# ArduinoISP_32U4_v3.net
KiCad netlist of a schematic drawn in EAGLE
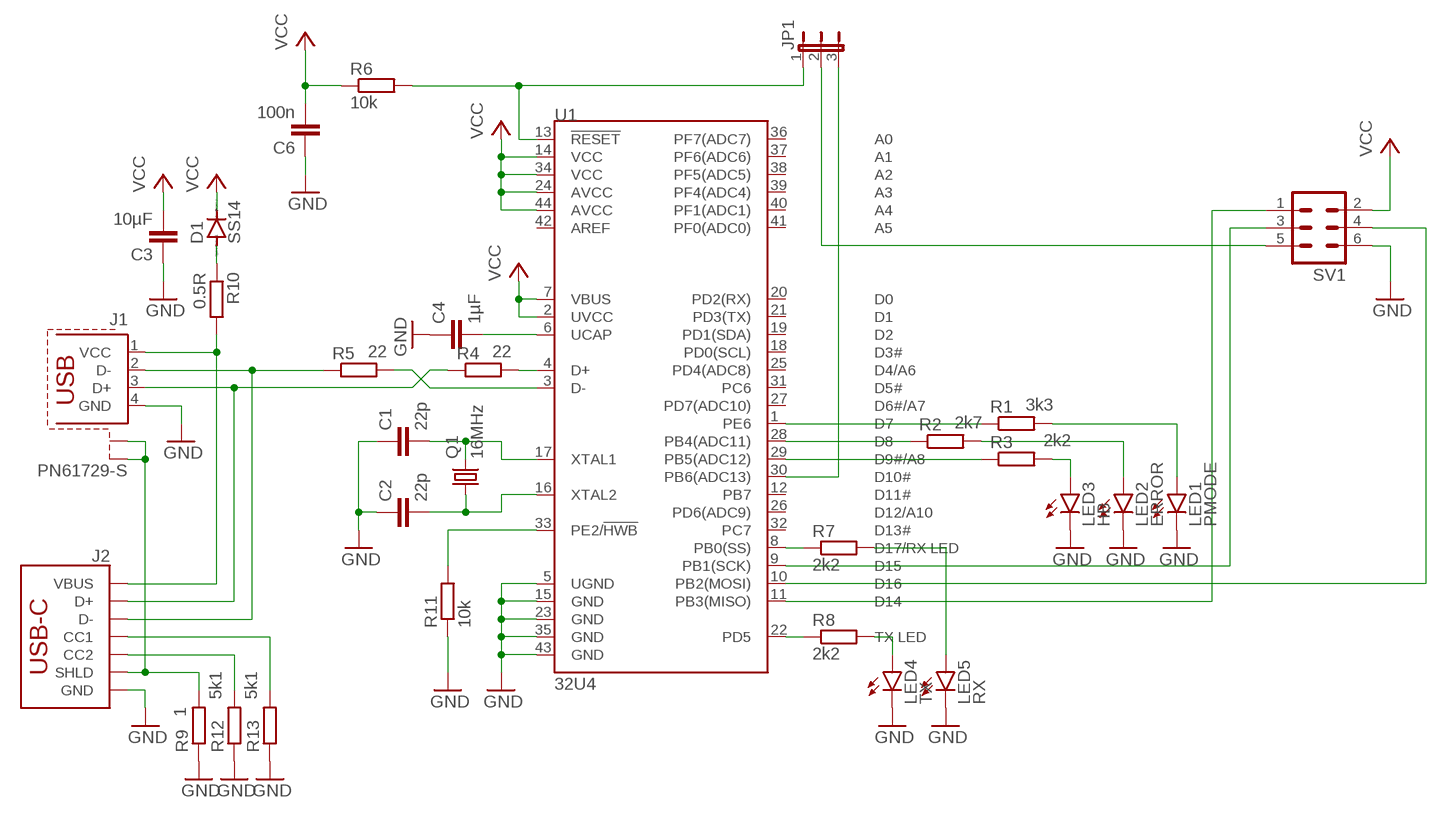
[diagram p0: schematic, sheet 1]

(export (version "E")
  (design (tool "Eeschema 10.0.6"))
  (components
    (comp (ref "C1")
      (value "22p")
      (footprint "eagle-import:C1206")
      (libsource (lib "eagle-import") (part "C-EUC1206"))
    )
    (comp (ref "C2")
      (value "22p")
      (footprint "eagle-import:C1206")
      (libsource (lib "eagle-import") (part "C-EUC1206"))
    )
    (comp (ref "C3")
      (value "10µF")
      (footprint "eagle-import:C1206")
      (libsource (lib "eagle-import") (part "C-EUC1206"))
    )
    (comp (ref "C4")
      (value "1µF")
      (footprint "eagle-import:C1206")
      (libsource (lib "eagle-import") (part "C-EUC1206"))
    )
    (comp (ref "C6")
      (value "100n")
      (footprint "eagle-import:C1206")
      (libsource (lib "eagle-import") (part "C-EUC1206"))
    )
    (comp (ref "D1")
      (value "SS14")
      (footprint "eagle-import:DO214AC")
      (libsource (lib "eagle-import") (part "DIODE-DO214AC"))
    )
    (comp (ref "J1")
      (value "PN61729-S")
      (footprint "eagle-import:PN61729-S")
      (libsource (lib "eagle-import") (part "PN61729-S"))
    )
    (comp (ref "J2")
      (value "USB_C_2-LAYER_PADS")
      (footprint "eagle-import:USB-C-16P-2LAYER-PADS")
      (libsource (lib "eagle-import") (part "USB_C_2-LAYER_PADS"))
    )
    (comp (ref "JP1")
      (value "JP2E")
      (footprint "eagle-import:JP2")
      (libsource (lib "eagle-import") (part "JP2E"))
    )
    (comp (ref "LED1")
      (value "PMODE")
      (footprint "eagle-import:CHIPLED_1206")
      (libsource (lib "eagle-import") (part "LEDCHIPLED_1206"))
    )
    (comp (ref "LED2")
      (value "ERROR")
      (footprint "eagle-import:CHIPLED_1206")
      (libsource (lib "eagle-import") (part "LEDCHIPLED_1206"))
    )
    (comp (ref "LED3")
      (value "HB")
      (footprint "eagle-import:CHIPLED_1206")
      (libsource (lib "eagle-import") (part "LEDCHIPLED_1206"))
    )
    (comp (ref "LED4")
      (value "TX")
      (footprint "eagle-import:CHIPLED_1206")
      (libsource (lib "eagle-import") (part "LEDCHIPLED_1206"))
    )
    (comp (ref "LED5")
      (value "RX")
      (footprint "eagle-import:CHIPLED_1206")
      (libsource (lib "eagle-import") (part "LEDCHIPLED_1206"))
    )
    (comp (ref "Q1")
      (value "16MHz")
      (footprint "eagle-import:HC49UP")
      (libsource (lib "eagle-import") (part "CRYSTALHC49UP"))
    )
    (comp (ref "R1")
      (value "3k3")
      (footprint "eagle-import:R1206")
      (libsource (lib "eagle-import") (part "R-EU_R1206"))
    )
    (comp (ref "R2")
      (value "2k7")
      (footprint "eagle-import:R1206")
      (libsource (lib "eagle-import") (part "R-EU_R1206"))
    )
    (comp (ref "R3")
      (value "2k2")
      (footprint "eagle-import:R1206")
      (libsource (lib "eagle-import") (part "R-EU_R1206"))
    )
    (comp (ref "R4")
      (value "22")
      (footprint "eagle-import:R1206")
      (libsource (lib "eagle-import") (part "R-EU_R1206"))
    )
    (comp (ref "R5")
      (value "22")
      (footprint "eagle-import:R1206")
      (libsource (lib "eagle-import") (part "R-EU_R1206"))
    )
    (comp (ref "R6")
      (value "10k")
      (footprint "eagle-import:R1206")
      (libsource (lib "eagle-import") (part "R-EU_R1206"))
    )
    (comp (ref "R7")
      (value "2k2")
      (footprint "eagle-import:R1206")
      (libsource (lib "eagle-import") (part "R-EU_R1206"))
    )
    (comp (ref "R8")
      (value "2k2")
      (footprint "eagle-import:R1206")
      (libsource (lib "eagle-import") (part "R-EU_R1206"))
    )
    (comp (ref "R9")
      (value "1")
      (footprint "eagle-import:R1206")
      (libsource (lib "eagle-import") (part "R-EU_R1206"))
    )
    (comp (ref "R10")
      (value "0.5R")
      (footprint "eagle-import:R1206")
      (libsource (lib "eagle-import") (part "R-EU_R1206"))
    )
    (comp (ref "R11")
      (value "10k")
      (footprint "eagle-import:R1206")
      (libsource (lib "eagle-import") (part "R-EU_R1206"))
    )
    (comp (ref "R12")
      (value "5k1")
      (footprint "eagle-import:R1206")
      (libsource (lib "eagle-import") (part "R-EU_R1206"))
    )
    (comp (ref "R13")
      (value "5k1")
      (footprint "eagle-import:R1206")
      (libsource (lib "eagle-import") (part "R-EU_R1206"))
    )
    (comp (ref "SV1")
      (value "ML6")
      (footprint "eagle-import:ML6")
      (libsource (lib "eagle-import") (part "ML6"))
    )
    (comp (ref "U1")
      (value "32U4")
      (footprint "eagle-import:TQFP44")
      (libsource (lib "eagle-import") (part "ATMEGA32U4TQFP-44"))
    )
  )
  (nets
    (net (code "1") (name "GND") (class "Default")
      (node (ref "C1") (pin "1") (pinfunction "1_1") (pintype "passive"))
      (node (ref "C2") (pin "1") (pinfunction "1_1") (pintype "passive"))
      (node (ref "C3") (pin "1") (pinfunction "1_1") (pintype "passive"))
      (node (ref "C4") (pin "1") (pinfunction "1_1") (pintype "passive"))
      (node (ref "C6") (pin "1") (pinfunction "1_1") (pintype "passive"))
      (node (ref "J1") (pin "4") (pinfunction "GND_4") (pintype "passive"))
      (node (ref "J2") (pin "GND") (pinfunction "GND_GND") (pintype "bidirectional"))
      (node (ref "J2") (pin "GND2") (pinfunction "GND_GND2") (pintype "bidirectional"))
      (node (ref "LED1") (pin "C") (pinfunction "C_C") (pintype "passive"))
      (node (ref "LED2") (pin "C") (pinfunction "C_C") (pintype "passive"))
      (node (ref "LED3") (pin "C") (pinfunction "C_C") (pintype "passive"))
      (node (ref "LED4") (pin "C") (pinfunction "C_C") (pintype "passive"))
      (node (ref "LED5") (pin "C") (pinfunction "C_C") (pintype "passive"))
      (node (ref "R11") (pin "1") (pinfunction "1_1") (pintype "passive"))
      (node (ref "R12") (pin "1") (pinfunction "1_1") (pintype "passive"))
      (node (ref "R13") (pin "1") (pinfunction "1_1") (pintype "passive"))
      (node (ref "R9") (pin "1") (pinfunction "1_1") (pintype "passive"))
      (node (ref "SV1") (pin "6") (pinfunction "6_6") (pintype "passive"))
      (node (ref "U1") (pin "15") (pinfunction "GND_15") (pintype "bidirectional"))
      (node (ref "U1") (pin "23") (pinfunction "GND_23") (pintype "bidirectional"))
      (node (ref "U1") (pin "35") (pinfunction "GND_35") (pintype "bidirectional"))
      (node (ref "U1") (pin "43") (pinfunction "GND_43") (pintype "bidirectional"))
      (node (ref "U1") (pin "5") (pinfunction "UGND_5") (pintype "bidirectional"))
    )
    (net (code "2") (name "Net-(D1-PadA)") (class "Default")
      (node (ref "D1") (pin "A") (pinfunction "A_A") (pintype "passive"))
      (node (ref "R10") (pin "1") (pinfunction "1_1") (pintype "passive"))
    )
    (net (code "3") (name "Net-(J1-D+)") (class "Default")
      (node (ref "J1") (pin "3") (pinfunction "D+_3") (pintype "passive"))
      (node (ref "J2") (pin "A6") (pinfunction "D+_A6") (pintype "bidirectional"))
      (node (ref "J2") (pin "B6") (pinfunction "D+_B6") (pintype "bidirectional"))
      (node (ref "R4") (pin "1") (pinfunction "1_1") (pintype "passive"))
    )
    (net (code "4") (name "Net-(J1-D-)") (class "Default")
      (node (ref "J1") (pin "2") (pinfunction "D-_2") (pintype "passive"))
      (node (ref "J2") (pin "A7") (pinfunction "D-_A7") (pintype "bidirectional"))
      (node (ref "J2") (pin "B7") (pinfunction "D-_B7") (pintype "bidirectional"))
      (node (ref "R5") (pin "1") (pinfunction "1_1") (pintype "passive"))
    )
    (net (code "5") (name "Net-(J1-PadS1)") (class "Default")
      (node (ref "J1") (pin "S1") (pinfunction "S1_S1") (pintype "passive"))
      (node (ref "J1") (pin "S2") (pinfunction "S2_S2") (pintype "passive"))
      (node (ref "J2") (pin "SHLD1") (pinfunction "SHLD_SHLD1") (pintype "bidirectional"))
      (node (ref "J2") (pin "SHLD2") (pinfunction "SHLD_SHLD2") (pintype "bidirectional"))
      (node (ref "J2") (pin "SHLD3") (pinfunction "SHLD_SHLD3") (pintype "bidirectional"))
      (node (ref "J2") (pin "SHLD4") (pinfunction "SHLD_SHLD4") (pintype "bidirectional"))
      (node (ref "R9") (pin "2") (pinfunction "2_2") (pintype "passive"))
    )
    (net (code "6") (name "Net-(J1-VCC)") (class "Default")
      (node (ref "J1") (pin "1") (pinfunction "VCC_1") (pintype "passive"))
      (node (ref "J2") (pin "VBUS1") (pinfunction "VBUS_VBUS1") (pintype "bidirectional"))
      (node (ref "J2") (pin "VBUS2") (pinfunction "VBUS_VBUS2") (pintype "bidirectional"))
      (node (ref "R10") (pin "2") (pinfunction "2_2") (pintype "passive"))
    )
    (net (code "7") (name "Net-(J2-CC1)") (class "Default")
      (node (ref "J2") (pin "A5") (pinfunction "CC1_A5") (pintype "bidirectional"))
      (node (ref "R13") (pin "2") (pinfunction "2_2") (pintype "passive"))
    )
    (net (code "8") (name "Net-(J2-CC2)") (class "Default")
      (node (ref "J2") (pin "B5") (pinfunction "CC2_B5") (pintype "bidirectional"))
      (node (ref "R12") (pin "2") (pinfunction "2_2") (pintype "passive"))
    )
    (net (code "9") (name "Net-(JP1-Pad2)") (class "Default")
      (node (ref "JP1") (pin "2") (pinfunction "2_2") (pintype "passive"))
      (node (ref "SV1") (pin "5") (pinfunction "5_5") (pintype "passive"))
    )
    (net (code "10") (name "Net-(LED1-PadA)") (class "Default")
      (node (ref "LED1") (pin "A") (pinfunction "A_A") (pintype "passive"))
      (node (ref "R1") (pin "2") (pinfunction "2_2") (pintype "passive"))
    )
    (net (code "11") (name "Net-(LED2-PadA)") (class "Default")
      (node (ref "LED2") (pin "A") (pinfunction "A_A") (pintype "passive"))
      (node (ref "R2") (pin "2") (pinfunction "2_2") (pintype "passive"))
    )
    (net (code "12") (name "Net-(LED3-PadA)") (class "Default")
      (node (ref "LED3") (pin "A") (pinfunction "A_A") (pintype "passive"))
      (node (ref "R3") (pin "2") (pinfunction "2_2") (pintype "passive"))
    )
    (net (code "13") (name "Net-(LED4-PadA)") (class "Default")
      (node (ref "LED4") (pin "A") (pinfunction "A_A") (pintype "passive"))
      (node (ref "R8") (pin "2") (pinfunction "2_2") (pintype "passive"))
    )
    (net (code "14") (name "Net-(LED5-PadA)") (class "Default")
      (node (ref "LED5") (pin "A") (pinfunction "A_A") (pintype "passive"))
      (node (ref "R7") (pin "2") (pinfunction "2_2") (pintype "passive"))
    )
    (net (code "15") (name "Net-(U1-D+)") (class "Default")
      (node (ref "R4") (pin "2") (pinfunction "2_2") (pintype "passive"))
      (node (ref "U1") (pin "4") (pinfunction "D+_4") (pintype "bidirectional"))
    )
    (net (code "16") (name "Net-(U1-D-)") (class "Default")
      (node (ref "R5") (pin "2") (pinfunction "2_2") (pintype "passive"))
      (node (ref "U1") (pin "3") (pinfunction "D-_3") (pintype "bidirectional"))
    )
    (net (code "17") (name "Net-(U1-PB0(SS))") (class "Default")
      (node (ref "R7") (pin "1") (pinfunction "1_1") (pintype "passive"))
      (node (ref "U1") (pin "8") (pinfunction "PB0(SS)_8") (pintype "bidirectional"))
    )
    (net (code "18") (name "Net-(U1-PB1(SCK))") (class "Default")
      (node (ref "SV1") (pin "3") (pinfunction "3_3") (pintype "passive"))
      (node (ref "U1") (pin "9") (pinfunction "PB1(SCK)_9") (pintype "bidirectional"))
    )
    (net (code "19") (name "Net-(U1-PB2(MOSI))") (class "Default")
      (node (ref "SV1") (pin "4") (pinfunction "4_4") (pintype "passive"))
      (node (ref "U1") (pin "10") (pinfunction "PB2(MOSI)_10") (pintype "bidirectional"))
    )
    (net (code "20") (name "Net-(U1-PB3(MISO))") (class "Default")
      (node (ref "SV1") (pin "1") (pinfunction "1_1") (pintype "passive"))
      (node (ref "U1") (pin "11") (pinfunction "PB3(MISO)_11") (pintype "bidirectional"))
    )
    (net (code "21") (name "Net-(U1-PB4(ADC11))") (class "Default")
      (node (ref "R2") (pin "1") (pinfunction "1_1") (pintype "passive"))
      (node (ref "U1") (pin "28") (pinfunction "PB4(ADC11)_28") (pintype "bidirectional"))
    )
    (net (code "22") (name "Net-(U1-PB5(ADC12))") (class "Default")
      (node (ref "R3") (pin "1") (pinfunction "1_1") (pintype "passive"))
      (node (ref "U1") (pin "29") (pinfunction "PB5(ADC12)_29") (pintype "bidirectional"))
    )
    (net (code "23") (name "Net-(U1-PB6(ADC13))") (class "Default")
      (node (ref "JP1") (pin "3") (pinfunction "3_3") (pintype "passive"))
      (node (ref "U1") (pin "30") (pinfunction "PB6(ADC13)_30") (pintype "bidirectional"))
    )
    (net (code "24") (name "Net-(U1-PD5)") (class "Default")
      (node (ref "R8") (pin "1") (pinfunction "1_1") (pintype "passive"))
      (node (ref "U1") (pin "22") (pinfunction "PD5_22") (pintype "bidirectional"))
    )
    (net (code "25") (name "Net-(U1-PE2{slash}~{HWB})") (class "Default")
      (node (ref "R11") (pin "2") (pinfunction "2_2") (pintype "passive"))
      (node (ref "U1") (pin "33") (pinfunction "PE2/~{HWB}_33") (pintype "bidirectional"))
    )
    (net (code "26") (name "Net-(U1-PE6)") (class "Default")
      (node (ref "R1") (pin "1") (pinfunction "1_1") (pintype "passive"))
      (node (ref "U1") (pin "1") (pinfunction "PE6_1") (pintype "bidirectional"))
    )
    (net (code "27") (name "Net-(U1-UCAP)") (class "Default")
      (node (ref "C4") (pin "2") (pinfunction "2_2") (pintype "passive"))
      (node (ref "U1") (pin "6") (pinfunction "UCAP_6") (pintype "bidirectional"))
    )
    (net (code "28") (name "Net-(U1-XTAL1)") (class "Default")
      (node (ref "C1") (pin "2") (pinfunction "2_2") (pintype "passive"))
      (node (ref "Q1") (pin "2") (pinfunction "2_2") (pintype "passive"))
      (node (ref "Q1") (pin "22") (pinfunction "2_22") (pintype "passive"))
      (node (ref "U1") (pin "17") (pinfunction "XTAL1_17") (pintype "bidirectional"))
    )
    (net (code "29") (name "Net-(U1-XTAL2)") (class "Default")
      (node (ref "C2") (pin "2") (pinfunction "2_2") (pintype "passive"))
      (node (ref "Q1") (pin "1") (pinfunction "1_1") (pintype "passive"))
      (node (ref "Q1") (pin "11") (pinfunction "1_11") (pintype "passive"))
      (node (ref "U1") (pin "16") (pinfunction "XTAL2_16") (pintype "bidirectional"))
    )
    (net (code "30") (name "Net-(U1-~{RESET})") (class "Default")
      (node (ref "JP1") (pin "1") (pinfunction "1_1") (pintype "passive"))
      (node (ref "R6") (pin "2") (pinfunction "2_2") (pintype "passive"))
      (node (ref "U1") (pin "13") (pinfunction "~{RESET}_13") (pintype "bidirectional"))
    )
    (net (code "31") (name "VCC") (class "Default")
      (node (ref "C3") (pin "2") (pinfunction "2_2") (pintype "passive"))
      (node (ref "C6") (pin "2") (pinfunction "2_2") (pintype "passive"))
      (node (ref "D1") (pin "C") (pinfunction "C_C") (pintype "passive"))
      (node (ref "R6") (pin "1") (pinfunction "1_1") (pintype "passive"))
      (node (ref "SV1") (pin "2") (pinfunction "2_2") (pintype "passive"))
      (node (ref "U1") (pin "14") (pinfunction "VCC_14") (pintype "bidirectional"))
      (node (ref "U1") (pin "2") (pinfunction "UVCC_2") (pintype "bidirectional"))
      (node (ref "U1") (pin "24") (pinfunction "AVCC_24") (pintype "bidirectional"))
      (node (ref "U1") (pin "34") (pinfunction "VCC_34") (pintype "bidirectional"))
      (node (ref "U1") (pin "44") (pinfunction "AVCC_44") (pintype "bidirectional"))
      (node (ref "U1") (pin "7") (pinfunction "VBUS_7") (pintype "bidirectional"))
    )
    (net (code "32") (name "unconnected-(U1-AREF-Pad42)") (class "Default")
      (node (ref "U1") (pin "42") (pinfunction "AREF_42") (pintype "bidirectional"))
    )
    (net (code "33") (name "unconnected-(U1-PB7-Pad12)") (class "Default")
      (node (ref "U1") (pin "12") (pinfunction "PB7_12") (pintype "bidirectional"))
    )
    (net (code "34") (name "unconnected-(U1-PC6-Pad31)") (class "Default")
      (node (ref "U1") (pin "31") (pinfunction "PC6_31") (pintype "bidirectional"))
    )
    (net (code "35") (name "unconnected-(U1-PC7-Pad32)") (class "Default")
      (node (ref "U1") (pin "32") (pinfunction "PC7_32") (pintype "bidirectional"))
    )
    (net (code "36") (name "unconnected-(U1-PD0(SCL)-Pad18)") (class "Default")
      (node (ref "U1") (pin "18") (pinfunction "PD0(SCL)_18") (pintype "bidirectional"))
    )
    (net (code "37") (name "unconnected-(U1-PD1(SDA)-Pad19)") (class "Default")
      (node (ref "U1") (pin "19") (pinfunction "PD1(SDA)_19") (pintype "bidirectional"))
    )
    (net (code "38") (name "unconnected-(U1-PD2(RX)-Pad20)") (class "Default")
      (node (ref "U1") (pin "20") (pinfunction "PD2(RX)_20") (pintype "bidirectional"))
    )
    (net (code "39") (name "unconnected-(U1-PD3(TX)-Pad21)") (class "Default")
      (node (ref "U1") (pin "21") (pinfunction "PD3(TX)_21") (pintype "bidirectional"))
    )
    (net (code "40") (name "unconnected-(U1-PD4(ADC8)-Pad25)") (class "Default")
      (node (ref "U1") (pin "25") (pinfunction "PD4(ADC8)_25") (pintype "bidirectional"))
    )
    (net (code "41") (name "unconnected-(U1-PD6(ADC9)-Pad26)") (class "Default")
      (node (ref "U1") (pin "26") (pinfunction "PD6(ADC9)_26") (pintype "bidirectional"))
    )
    (net (code "42") (name "unconnected-(U1-PD7(ADC10)-Pad27)") (class "Default")
      (node (ref "U1") (pin "27") (pinfunction "PD7(ADC10)_27") (pintype "bidirectional"))
    )
    (net (code "43") (name "unconnected-(U1-PF0(ADC0)-Pad41)") (class "Default")
      (node (ref "U1") (pin "41") (pinfunction "PF0(ADC0)_41") (pintype "bidirectional"))
    )
    (net (code "44") (name "unconnected-(U1-PF1(ADC1)-Pad40)") (class "Default")
      (node (ref "U1") (pin "40") (pinfunction "PF1(ADC1)_40") (pintype "bidirectional"))
    )
    (net (code "45") (name "unconnected-(U1-PF4(ADC4)-Pad39)") (class "Default")
      (node (ref "U1") (pin "39") (pinfunction "PF4(ADC4)_39") (pintype "bidirectional"))
    )
    (net (code "46") (name "unconnected-(U1-PF5(ADC5)-Pad38)") (class "Default")
      (node (ref "U1") (pin "38") (pinfunction "PF5(ADC5)_38") (pintype "bidirectional"))
    )
    (net (code "47") (name "unconnected-(U1-PF6(ADC6)-Pad37)") (class "Default")
      (node (ref "U1") (pin "37") (pinfunction "PF6(ADC6)_37") (pintype "bidirectional"))
    )
    (net (code "48") (name "unconnected-(U1-PF7(ADC7)-Pad36)") (class "Default")
      (node (ref "U1") (pin "36") (pinfunction "PF7(ADC7)_36") (pintype "bidirectional"))
    )
  )
)
